# untitled.net
KiCad netlist of a schematic drawn in EAGLE
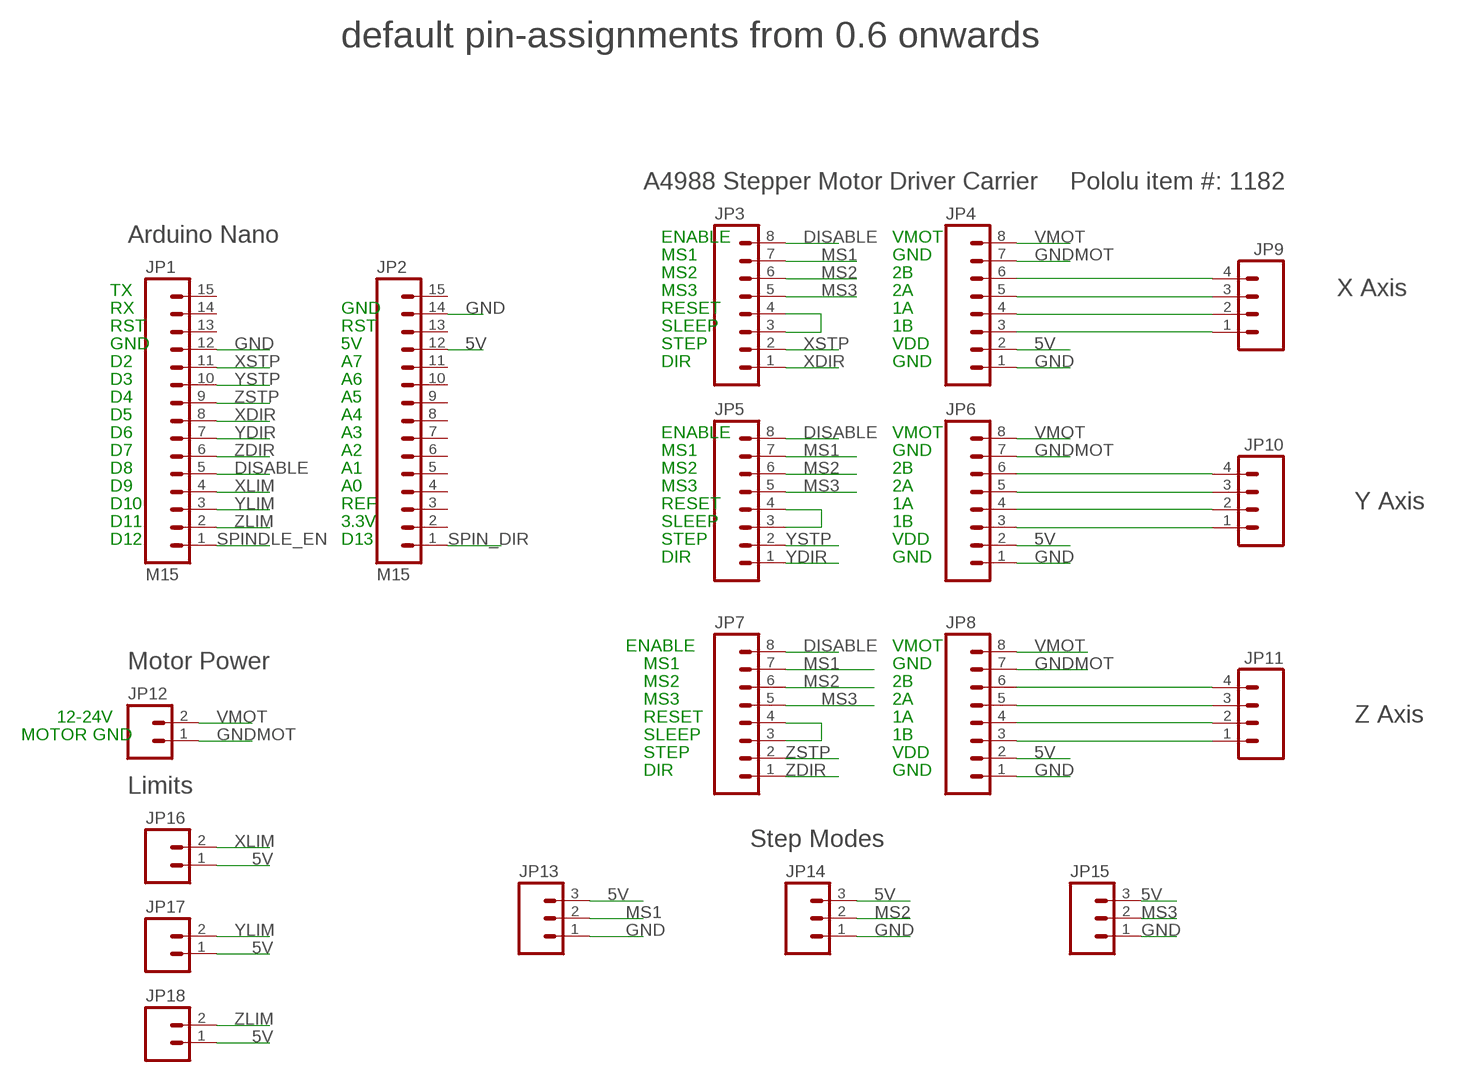
[diagram p0: schematic, sheet 1]

(export (version "E")
  (design (tool "Eeschema 10.0.6"))
  (components
    (comp (ref "JP1")
      (value "M15")
      (footprint "eagle-import:1X15")
      (libsource (lib "eagle-import") (part "M15"))
    )
    (comp (ref "JP2")
      (value "M15")
      (footprint "eagle-import:1X15")
      (libsource (lib "eagle-import") (part "M15"))
    )
    (comp (ref "JP3")
      (value "M08LONGPADS")
      (footprint "eagle-import:1X08_LONGPADS")
      (libsource (lib "eagle-import") (part "M08LONGPADS"))
    )
    (comp (ref "JP4")
      (value "M08LONGPADS")
      (footprint "eagle-import:1X08_LONGPADS")
      (libsource (lib "eagle-import") (part "M08LONGPADS"))
    )
    (comp (ref "JP5")
      (value "M08LONGPADS")
      (footprint "eagle-import:1X08_LONGPADS")
      (libsource (lib "eagle-import") (part "M08LONGPADS"))
    )
    (comp (ref "JP6")
      (value "M08LONGPADS")
      (footprint "eagle-import:1X08_LONGPADS")
      (libsource (lib "eagle-import") (part "M08LONGPADS"))
    )
    (comp (ref "JP7")
      (value "M08LONGPADS")
      (footprint "eagle-import:1X08_LONGPADS")
      (libsource (lib "eagle-import") (part "M08LONGPADS"))
    )
    (comp (ref "JP8")
      (value "M08LONGPADS")
      (footprint "eagle-import:1X08_LONGPADS")
      (libsource (lib "eagle-import") (part "M08LONGPADS"))
    )
    (comp (ref "JP9")
      (value "M04LONGPADS")
      (footprint "eagle-import:1X04_LONGPADS")
      (libsource (lib "eagle-import") (part "M04LONGPADS"))
    )
    (comp (ref "JP10")
      (value "M04LONGPADS")
      (footprint "eagle-import:1X04_LONGPADS")
      (libsource (lib "eagle-import") (part "M04LONGPADS"))
    )
    (comp (ref "JP11")
      (value "M04LONGPADS")
      (footprint "eagle-import:1X04_LONGPADS")
      (libsource (lib "eagle-import") (part "M04LONGPADS"))
    )
    (comp (ref "JP12")
      (value "M02LOCK_LONGPADS")
      (footprint "eagle-import:1X02_LOCK_LONGPADS")
      (libsource (lib "eagle-import") (part "M02LOCK_LONGPADS"))
    )
    (comp (ref "JP13")
      (value "M03PTH")
      (footprint "eagle-import:1X03")
      (libsource (lib "eagle-import") (part "M03PTH"))
    )
    (comp (ref "JP14")
      (value "M03PTH")
      (footprint "eagle-import:1X03")
      (libsource (lib "eagle-import") (part "M03PTH"))
    )
    (comp (ref "JP15")
      (value "M03PTH")
      (footprint "eagle-import:1X03")
      (libsource (lib "eagle-import") (part "M03PTH"))
    )
    (comp (ref "JP16")
      (value "M02LOCK_LONGPADS")
      (footprint "eagle-import:1X02_LOCK_LONGPADS")
      (libsource (lib "eagle-import") (part "M02LOCK_LONGPADS"))
    )
    (comp (ref "JP17")
      (value "M02LOCK_LONGPADS")
      (footprint "eagle-import:1X02_LOCK_LONGPADS")
      (libsource (lib "eagle-import") (part "M02LOCK_LONGPADS"))
    )
    (comp (ref "JP18")
      (value "M02LOCK_LONGPADS")
      (footprint "eagle-import:1X02_LOCK_LONGPADS")
      (libsource (lib "eagle-import") (part "M02LOCK_LONGPADS"))
    )
  )
  (nets
    (net (code "1") (name "/5V") (class "Default")
      (node (ref "JP13") (pin "3") (pinfunction "3_3") (pintype "passive"))
      (node (ref "JP14") (pin "3") (pinfunction "3_3") (pintype "passive"))
      (node (ref "JP15") (pin "3") (pinfunction "3_3") (pintype "passive"))
      (node (ref "JP16") (pin "1") (pinfunction "1_1") (pintype "passive"))
      (node (ref "JP17") (pin "1") (pinfunction "1_1") (pintype "passive"))
      (node (ref "JP18") (pin "1") (pinfunction "1_1") (pintype "passive"))
      (node (ref "JP2") (pin "12") (pinfunction "12_12") (pintype "passive"))
      (node (ref "JP4") (pin "2") (pinfunction "2_2") (pintype "passive"))
      (node (ref "JP6") (pin "2") (pinfunction "2_2") (pintype "passive"))
      (node (ref "JP8") (pin "2") (pinfunction "2_2") (pintype "passive"))
    )
    (net (code "2") (name "/DISABLE") (class "Default")
      (node (ref "JP1") (pin "5") (pinfunction "5_5") (pintype "passive"))
      (node (ref "JP3") (pin "8") (pinfunction "8_8") (pintype "passive"))
      (node (ref "JP5") (pin "8") (pinfunction "8_8") (pintype "passive"))
      (node (ref "JP7") (pin "8") (pinfunction "8_8") (pintype "passive"))
    )
    (net (code "3") (name "/GND") (class "Default")
      (node (ref "JP1") (pin "12") (pinfunction "12_12") (pintype "passive"))
      (node (ref "JP13") (pin "1") (pinfunction "1_1") (pintype "passive"))
      (node (ref "JP14") (pin "1") (pinfunction "1_1") (pintype "passive"))
      (node (ref "JP15") (pin "1") (pinfunction "1_1") (pintype "passive"))
      (node (ref "JP2") (pin "14") (pinfunction "14_14") (pintype "passive"))
      (node (ref "JP4") (pin "1") (pinfunction "1_1") (pintype "passive"))
      (node (ref "JP6") (pin "1") (pinfunction "1_1") (pintype "passive"))
      (node (ref "JP8") (pin "1") (pinfunction "1_1") (pintype "passive"))
    )
    (net (code "4") (name "/GNDMOT") (class "Default")
      (node (ref "JP12") (pin "1") (pinfunction "1_1") (pintype "passive"))
      (node (ref "JP4") (pin "7") (pinfunction "7_7") (pintype "passive"))
      (node (ref "JP6") (pin "7") (pinfunction "7_7") (pintype "passive"))
      (node (ref "JP8") (pin "7") (pinfunction "7_7") (pintype "passive"))
    )
    (net (code "5") (name "/MS1") (class "Default")
      (node (ref "JP13") (pin "2") (pinfunction "2_2") (pintype "passive"))
      (node (ref "JP3") (pin "7") (pinfunction "7_7") (pintype "passive"))
      (node (ref "JP5") (pin "7") (pinfunction "7_7") (pintype "passive"))
      (node (ref "JP7") (pin "7") (pinfunction "7_7") (pintype "passive"))
    )
    (net (code "6") (name "/MS2") (class "Default")
      (node (ref "JP14") (pin "2") (pinfunction "2_2") (pintype "passive"))
      (node (ref "JP3") (pin "6") (pinfunction "6_6") (pintype "passive"))
      (node (ref "JP5") (pin "6") (pinfunction "6_6") (pintype "passive"))
      (node (ref "JP7") (pin "6") (pinfunction "6_6") (pintype "passive"))
    )
    (net (code "7") (name "/MS3") (class "Default")
      (node (ref "JP15") (pin "2") (pinfunction "2_2") (pintype "passive"))
      (node (ref "JP3") (pin "5") (pinfunction "5_5") (pintype "passive"))
      (node (ref "JP5") (pin "5") (pinfunction "5_5") (pintype "passive"))
      (node (ref "JP7") (pin "5") (pinfunction "5_5") (pintype "passive"))
    )
    (net (code "8") (name "/SPINDLE_EN") (class "Default")
      (node (ref "JP1") (pin "1") (pinfunction "1_1") (pintype "passive"))
    )
    (net (code "9") (name "/SPIN_DIR") (class "Default")
      (node (ref "JP2") (pin "1") (pinfunction "1_1") (pintype "passive"))
    )
    (net (code "10") (name "/VMOT") (class "Default")
      (node (ref "JP12") (pin "2") (pinfunction "2_2") (pintype "passive"))
      (node (ref "JP4") (pin "8") (pinfunction "8_8") (pintype "passive"))
      (node (ref "JP6") (pin "8") (pinfunction "8_8") (pintype "passive"))
      (node (ref "JP8") (pin "8") (pinfunction "8_8") (pintype "passive"))
    )
    (net (code "11") (name "/XDIR") (class "Default")
      (node (ref "JP1") (pin "8") (pinfunction "8_8") (pintype "passive"))
      (node (ref "JP3") (pin "1") (pinfunction "1_1") (pintype "passive"))
    )
    (net (code "12") (name "/XLIM") (class "Default")
      (node (ref "JP1") (pin "4") (pinfunction "4_4") (pintype "passive"))
      (node (ref "JP16") (pin "2") (pinfunction "2_2") (pintype "passive"))
    )
    (net (code "13") (name "/XSTP") (class "Default")
      (node (ref "JP1") (pin "11") (pinfunction "11_11") (pintype "passive"))
      (node (ref "JP3") (pin "2") (pinfunction "2_2") (pintype "passive"))
    )
    (net (code "14") (name "/YDIR") (class "Default")
      (node (ref "JP1") (pin "7") (pinfunction "7_7") (pintype "passive"))
      (node (ref "JP5") (pin "1") (pinfunction "1_1") (pintype "passive"))
    )
    (net (code "15") (name "/YLIM") (class "Default")
      (node (ref "JP1") (pin "3") (pinfunction "3_3") (pintype "passive"))
      (node (ref "JP17") (pin "2") (pinfunction "2_2") (pintype "passive"))
    )
    (net (code "16") (name "/YSTP") (class "Default")
      (node (ref "JP1") (pin "10") (pinfunction "10_10") (pintype "passive"))
      (node (ref "JP5") (pin "2") (pinfunction "2_2") (pintype "passive"))
    )
    (net (code "17") (name "/ZDIR") (class "Default")
      (node (ref "JP1") (pin "6") (pinfunction "6_6") (pintype "passive"))
      (node (ref "JP7") (pin "1") (pinfunction "1_1") (pintype "passive"))
    )
    (net (code "18") (name "/ZLIM") (class "Default")
      (node (ref "JP1") (pin "2") (pinfunction "2_2") (pintype "passive"))
      (node (ref "JP18") (pin "2") (pinfunction "2_2") (pintype "passive"))
    )
    (net (code "19") (name "/ZSTP") (class "Default")
      (node (ref "JP1") (pin "9") (pinfunction "9_9") (pintype "passive"))
      (node (ref "JP7") (pin "2") (pinfunction "2_2") (pintype "passive"))
    )
    (net (code "20") (name "Net-(JP3-Pad3)") (class "Default")
      (node (ref "JP3") (pin "3") (pinfunction "3_3") (pintype "passive"))
      (node (ref "JP3") (pin "4") (pinfunction "4_4") (pintype "passive"))
    )
    (net (code "21") (name "Net-(JP4-Pad3)") (class "Default")
      (node (ref "JP4") (pin "3") (pinfunction "3_3") (pintype "passive"))
      (node (ref "JP9") (pin "1") (pinfunction "1_1") (pintype "passive"))
    )
    (net (code "22") (name "Net-(JP4-Pad4)") (class "Default")
      (node (ref "JP4") (pin "4") (pinfunction "4_4") (pintype "passive"))
      (node (ref "JP9") (pin "2") (pinfunction "2_2") (pintype "passive"))
    )
    (net (code "23") (name "Net-(JP4-Pad5)") (class "Default")
      (node (ref "JP4") (pin "5") (pinfunction "5_5") (pintype "passive"))
      (node (ref "JP9") (pin "3") (pinfunction "3_3") (pintype "passive"))
    )
    (net (code "24") (name "Net-(JP4-Pad6)") (class "Default")
      (node (ref "JP4") (pin "6") (pinfunction "6_6") (pintype "passive"))
      (node (ref "JP9") (pin "4") (pinfunction "4_4") (pintype "passive"))
    )
    (net (code "25") (name "Net-(JP5-Pad3)") (class "Default")
      (node (ref "JP5") (pin "3") (pinfunction "3_3") (pintype "passive"))
      (node (ref "JP5") (pin "4") (pinfunction "4_4") (pintype "passive"))
    )
    (net (code "26") (name "Net-(JP7-Pad3)") (class "Default")
      (node (ref "JP7") (pin "3") (pinfunction "3_3") (pintype "passive"))
      (node (ref "JP7") (pin "4") (pinfunction "4_4") (pintype "passive"))
    )
    (net (code "27") (name "Net-(JP10-Pad1)") (class "Default")
      (node (ref "JP10") (pin "1") (pinfunction "1_1") (pintype "passive"))
      (node (ref "JP6") (pin "3") (pinfunction "3_3") (pintype "passive"))
    )
    (net (code "28") (name "Net-(JP10-Pad2)") (class "Default")
      (node (ref "JP10") (pin "2") (pinfunction "2_2") (pintype "passive"))
      (node (ref "JP6") (pin "4") (pinfunction "4_4") (pintype "passive"))
    )
    (net (code "29") (name "Net-(JP10-Pad3)") (class "Default")
      (node (ref "JP10") (pin "3") (pinfunction "3_3") (pintype "passive"))
      (node (ref "JP6") (pin "5") (pinfunction "5_5") (pintype "passive"))
    )
    (net (code "30") (name "Net-(JP10-Pad4)") (class "Default")
      (node (ref "JP10") (pin "4") (pinfunction "4_4") (pintype "passive"))
      (node (ref "JP6") (pin "6") (pinfunction "6_6") (pintype "passive"))
    )
    (net (code "31") (name "Net-(JP11-Pad1)") (class "Default")
      (node (ref "JP11") (pin "1") (pinfunction "1_1") (pintype "passive"))
      (node (ref "JP8") (pin "3") (pinfunction "3_3") (pintype "passive"))
    )
    (net (code "32") (name "Net-(JP11-Pad2)") (class "Default")
      (node (ref "JP11") (pin "2") (pinfunction "2_2") (pintype "passive"))
      (node (ref "JP8") (pin "4") (pinfunction "4_4") (pintype "passive"))
    )
    (net (code "33") (name "Net-(JP11-Pad3)") (class "Default")
      (node (ref "JP11") (pin "3") (pinfunction "3_3") (pintype "passive"))
      (node (ref "JP8") (pin "5") (pinfunction "5_5") (pintype "passive"))
    )
    (net (code "34") (name "Net-(JP11-Pad4)") (class "Default")
      (node (ref "JP11") (pin "4") (pinfunction "4_4") (pintype "passive"))
      (node (ref "JP8") (pin "6") (pinfunction "6_6") (pintype "passive"))
    )
    (net (code "35") (name "unconnected-(JP1-Pad13)") (class "Default")
      (node (ref "JP1") (pin "13") (pinfunction "13_13") (pintype "passive"))
    )
    (net (code "36") (name "unconnected-(JP1-Pad14)") (class "Default")
      (node (ref "JP1") (pin "14") (pinfunction "14_14") (pintype "passive"))
    )
    (net (code "37") (name "unconnected-(JP1-Pad15)") (class "Default")
      (node (ref "JP1") (pin "15") (pinfunction "15_15") (pintype "passive"))
    )
    (net (code "38") (name "unconnected-(JP2-Pad2)") (class "Default")
      (node (ref "JP2") (pin "2") (pinfunction "2_2") (pintype "passive"))
    )
    (net (code "39") (name "unconnected-(JP2-Pad3)") (class "Default")
      (node (ref "JP2") (pin "3") (pinfunction "3_3") (pintype "passive"))
    )
    (net (code "40") (name "unconnected-(JP2-Pad4)") (class "Default")
      (node (ref "JP2") (pin "4") (pinfunction "4_4") (pintype "passive"))
    )
    (net (code "41") (name "unconnected-(JP2-Pad5)") (class "Default")
      (node (ref "JP2") (pin "5") (pinfunction "5_5") (pintype "passive"))
    )
    (net (code "42") (name "unconnected-(JP2-Pad6)") (class "Default")
      (node (ref "JP2") (pin "6") (pinfunction "6_6") (pintype "passive"))
    )
    (net (code "43") (name "unconnected-(JP2-Pad7)") (class "Default")
      (node (ref "JP2") (pin "7") (pinfunction "7_7") (pintype "passive"))
    )
    (net (code "44") (name "unconnected-(JP2-Pad8)") (class "Default")
      (node (ref "JP2") (pin "8") (pinfunction "8_8") (pintype "passive"))
    )
    (net (code "45") (name "unconnected-(JP2-Pad9)") (class "Default")
      (node (ref "JP2") (pin "9") (pinfunction "9_9") (pintype "passive"))
    )
    (net (code "46") (name "unconnected-(JP2-Pad10)") (class "Default")
      (node (ref "JP2") (pin "10") (pinfunction "10_10") (pintype "passive"))
    )
    (net (code "47") (name "unconnected-(JP2-Pad11)") (class "Default")
      (node (ref "JP2") (pin "11") (pinfunction "11_11") (pintype "passive"))
    )
    (net (code "48") (name "unconnected-(JP2-Pad13)") (class "Default")
      (node (ref "JP2") (pin "13") (pinfunction "13_13") (pintype "passive"))
    )
    (net (code "49") (name "unconnected-(JP2-Pad15)") (class "Default")
      (node (ref "JP2") (pin "15") (pinfunction "15_15") (pintype "passive"))
    )
  )
)
